# MouseBox_PortBreakout_r1.net
KiCad netlist of a schematic drawn in EAGLE
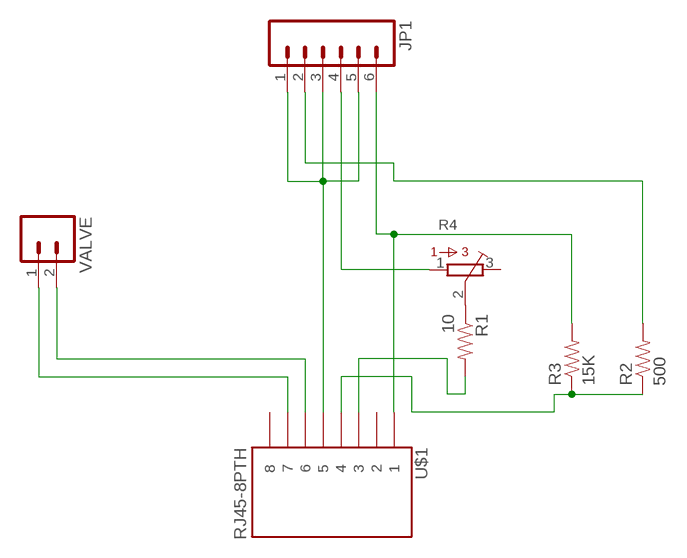
[diagram p0: schematic, sheet 1]

(export (version "E")
  (design (tool "Eeschema 10.0.6"))
  (components
    (comp (ref "JP1")
      (value "M063.5MM-6")
      (footprint "eagle-import:SCREWTERMINAL-3.5MM-6")
      (libsource (lib "eagle-import") (part "M063.5MM-6"))
    )
    (comp (ref "R1")
      (value "10")
      (footprint "eagle-import:AXIAL-0.3")
      (libsource (lib "eagle-import") (part "RESISTORAXIAL-0.3"))
    )
    (comp (ref "R2")
      (value "500")
      (footprint "eagle-import:AXIAL-0.3")
      (libsource (lib "eagle-import") (part "RESISTORAXIAL-0.3"))
    )
    (comp (ref "R3")
      (value "15K")
      (footprint "eagle-import:AXIAL-0.3")
      (libsource (lib "eagle-import") (part "RESISTORAXIAL-0.3"))
    )
    (comp (ref "R4")
      (value "3362R")
      (footprint "eagle-import:3362R")
      (libsource (lib "eagle-import") (part "3362R"))
    )
    (comp (ref "U$1")
      (value "RJ45-8PTH")
      (footprint "eagle-import:RJ45-8")
      (libsource (lib "eagle-import") (part "RJ45-8PTH"))
    )
    (comp (ref "VALVE")
      (value "M023.5MM_LOCK")
      (footprint "eagle-import:SCREWTERMINAL-3.5MM-2_LOCK")
      (libsource (lib "eagle-import") (part "M023.5MM_LOCK"))
    )
  )
  (nets
    (net (code "1") (name "Net-(JP1-Pad1)") (class "Default")
      (node (ref "JP1") (pin "1") (pinfunction "1_1") (pintype "passive"))
      (node (ref "JP1") (pin "3") (pinfunction "3_3") (pintype "passive"))
      (node (ref "JP1") (pin "5") (pinfunction "5_5") (pintype "passive"))
      (node (ref "U$1") (pin "5") (pinfunction "5_5") (pintype "bidirectional"))
    )
    (net (code "2") (name "Net-(JP1-Pad4)") (class "Default")
      (node (ref "JP1") (pin "4") (pinfunction "4_4") (pintype "passive"))
      (node (ref "R4") (pin "1") (pinfunction "1_1") (pintype "passive"))
    )
    (net (code "3") (name "Net-(R1-1)") (class "Default")
      (node (ref "R1") (pin "P$1") (pinfunction "1_P$1") (pintype "passive"))
      (node (ref "R4") (pin "2") (pinfunction "2_2") (pintype "passive"))
    )
    (net (code "4") (name "Net-(R1-2)") (class "Default")
      (node (ref "R1") (pin "P$2") (pinfunction "2_P$2") (pintype "passive"))
      (node (ref "U$1") (pin "3") (pinfunction "3_3") (pintype "bidirectional"))
    )
    (net (code "5") (name "Net-(R2-1)") (class "Default")
      (node (ref "R2") (pin "P$1") (pinfunction "1_P$1") (pintype "passive"))
      (node (ref "R3") (pin "P$1") (pinfunction "1_P$1") (pintype "passive"))
      (node (ref "U$1") (pin "4") (pinfunction "4_4") (pintype "bidirectional"))
    )
    (net (code "6") (name "Net-(R2-2)") (class "Default")
      (node (ref "JP1") (pin "2") (pinfunction "2_2") (pintype "passive"))
      (node (ref "R2") (pin "P$2") (pinfunction "2_P$2") (pintype "passive"))
    )
    (net (code "7") (name "Net-(R3-2)") (class "Default")
      (node (ref "JP1") (pin "6") (pinfunction "6_6") (pintype "passive"))
      (node (ref "R3") (pin "P$2") (pinfunction "2_P$2") (pintype "passive"))
      (node (ref "U$1") (pin "1") (pinfunction "1_1") (pintype "bidirectional"))
    )
    (net (code "8") (name "Net-(U$1-Pad6)") (class "Default")
      (node (ref "U$1") (pin "6") (pinfunction "6_6") (pintype "bidirectional"))
      (node (ref "VALVE") (pin "2") (pinfunction "2_2") (pintype "passive"))
    )
    (net (code "9") (name "Net-(U$1-Pad7)") (class "Default")
      (node (ref "U$1") (pin "7") (pinfunction "7_7") (pintype "bidirectional"))
      (node (ref "VALVE") (pin "1") (pinfunction "1_1") (pintype "passive"))
    )
    (net (code "10") (name "unconnected-(R4-Pad3)") (class "Default")
      (node (ref "R4") (pin "3") (pinfunction "3_3") (pintype "passive"))
    )
    (net (code "11") (name "unconnected-(U$1-Pad2)") (class "Default")
      (node (ref "U$1") (pin "2") (pinfunction "2_2") (pintype "bidirectional"))
    )
    (net (code "12") (name "unconnected-(U$1-Pad8)") (class "Default")
      (node (ref "U$1") (pin "8") (pinfunction "8_8") (pintype "bidirectional"))
    )
  )
)
